# Timer-Ruler_CR2032_on_bottom.net
KiCad netlist of a schematic drawn in EAGLE
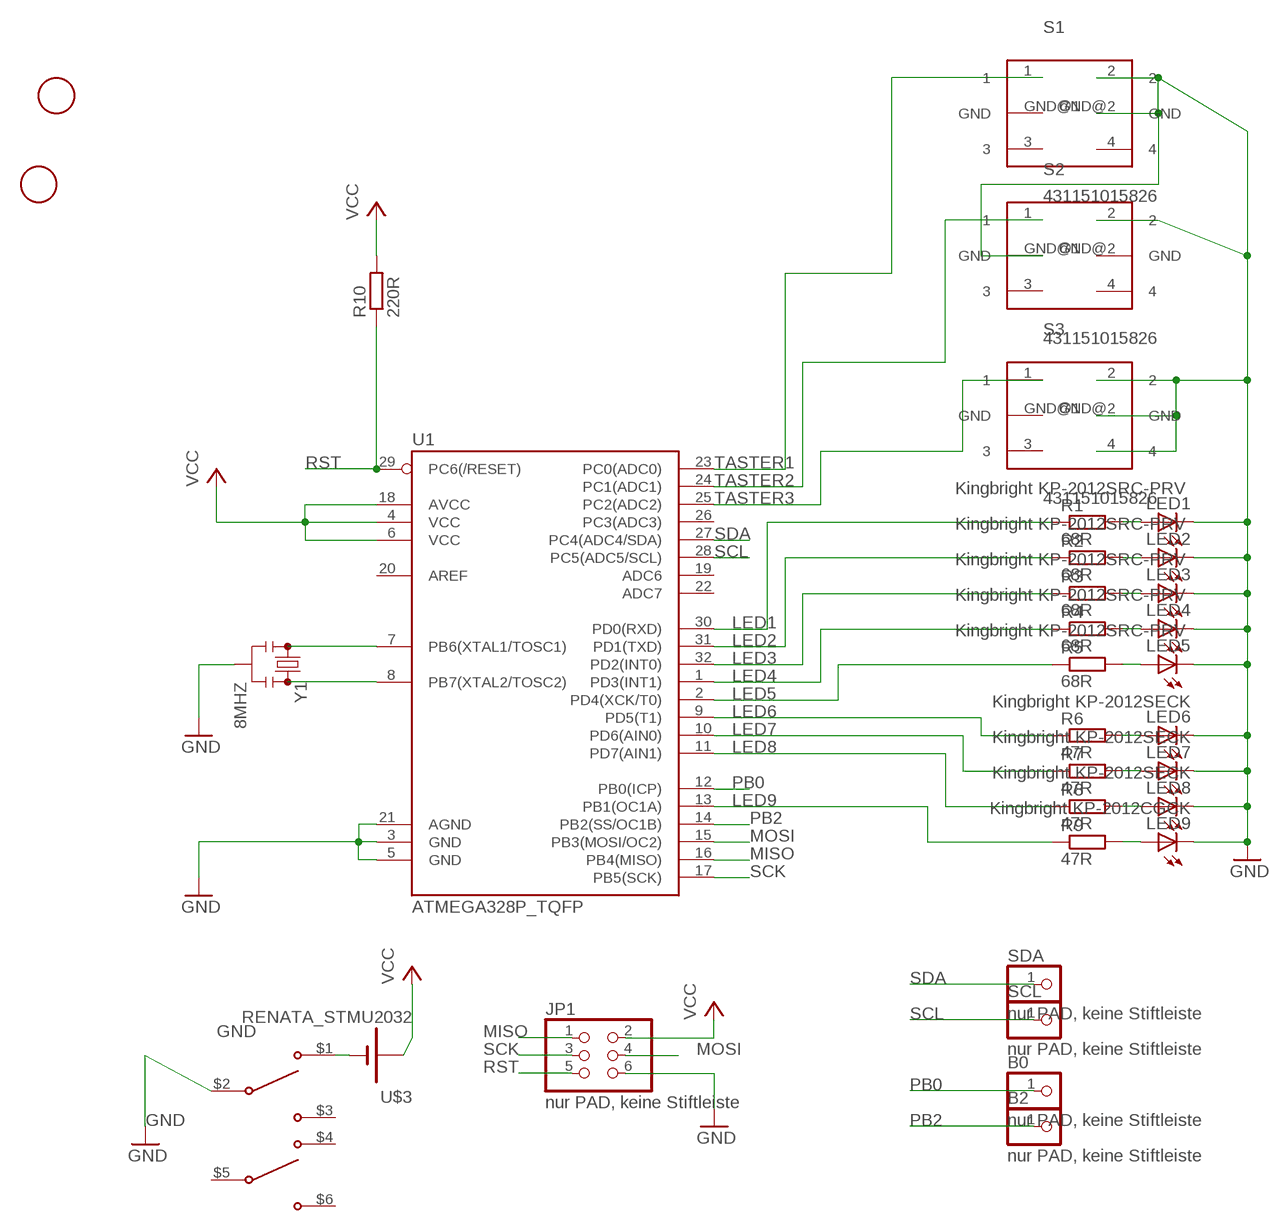
[diagram p0: schematic, sheet 1]

(export (version "E")
  (design (tool "Eeschema 10.0.6"))
  (components
    (comp (ref "B0")
      (value "nur PAD, keine Stiftleiste")
      (footprint "eagle-import:1X01")
      (libsource (lib "eagle-import") (part "PINHD-1X1"))
    )
    (comp (ref "B2")
      (value "nur PAD, keine Stiftleiste")
      (footprint "eagle-import:1X01")
      (libsource (lib "eagle-import") (part "PINHD-1X1"))
    )
    (comp (ref "JP1")
      (value "nur PAD, keine Stiftleiste")
      (footprint "eagle-import:2X03")
      (libsource (lib "eagle-import") (part "PINHD-2X3"))
    )
    (comp (ref "LED1")
      (value "Kingbright KP-2012SRC-PRV")
      (footprint "eagle-import:CHIP-LED0805")
      (libsource (lib "eagle-import") (part "LEDCHIP-LED0805"))
    )
    (comp (ref "LED2")
      (value "Kingbright KP-2012SRC-PRV")
      (footprint "eagle-import:CHIP-LED0805")
      (libsource (lib "eagle-import") (part "LEDCHIP-LED0805"))
    )
    (comp (ref "LED3")
      (value "Kingbright KP-2012SRC-PRV")
      (footprint "eagle-import:CHIP-LED0805")
      (libsource (lib "eagle-import") (part "LEDCHIP-LED0805"))
    )
    (comp (ref "LED4")
      (value "Kingbright KP-2012SRC-PRV")
      (footprint "eagle-import:CHIP-LED0805")
      (libsource (lib "eagle-import") (part "LEDCHIP-LED0805"))
    )
    (comp (ref "LED5")
      (value "Kingbright KP-2012SRC-PRV")
      (footprint "eagle-import:CHIP-LED0805")
      (libsource (lib "eagle-import") (part "LEDCHIP-LED0805"))
    )
    (comp (ref "LED6")
      (value "Kingbright KP-2012SECK")
      (footprint "eagle-import:CHIP-LED0805")
      (libsource (lib "eagle-import") (part "LEDCHIP-LED0805"))
    )
    (comp (ref "LED7")
      (value "Kingbright KP-2012SECK")
      (footprint "eagle-import:CHIP-LED0805")
      (libsource (lib "eagle-import") (part "LEDCHIP-LED0805"))
    )
    (comp (ref "LED8")
      (value "Kingbright KP-2012SECK")
      (footprint "eagle-import:CHIP-LED0805")
      (libsource (lib "eagle-import") (part "LEDCHIP-LED0805"))
    )
    (comp (ref "LED9")
      (value "Kingbright KP-2012CGCK")
      (footprint "eagle-import:CHIP-LED0805")
      (libsource (lib "eagle-import") (part "LEDCHIP-LED0805"))
    )
    (comp (ref "R1")
      (value "68R")
      (footprint "eagle-import:R0402")
      (libsource (lib "eagle-import") (part "R-EU_R0402"))
    )
    (comp (ref "R2")
      (value "68R")
      (footprint "eagle-import:R0402")
      (libsource (lib "eagle-import") (part "R-EU_R0402"))
    )
    (comp (ref "R3")
      (value "68R")
      (footprint "eagle-import:R0402")
      (libsource (lib "eagle-import") (part "R-EU_R0402"))
    )
    (comp (ref "R4")
      (value "68R")
      (footprint "eagle-import:R0402")
      (libsource (lib "eagle-import") (part "R-EU_R0402"))
    )
    (comp (ref "R5")
      (value "68R")
      (footprint "eagle-import:R0402")
      (libsource (lib "eagle-import") (part "R-EU_R0402"))
    )
    (comp (ref "R6")
      (value "47R")
      (footprint "eagle-import:R0402")
      (libsource (lib "eagle-import") (part "R-EU_R0402"))
    )
    (comp (ref "R7")
      (value "47R")
      (footprint "eagle-import:R0402")
      (libsource (lib "eagle-import") (part "R-EU_R0402"))
    )
    (comp (ref "R8")
      (value "47R")
      (footprint "eagle-import:R0402")
      (libsource (lib "eagle-import") (part "R-EU_R0402"))
    )
    (comp (ref "R9")
      (value "47R")
      (footprint "eagle-import:R0402")
      (libsource (lib "eagle-import") (part "R-EU_R0402"))
    )
    (comp (ref "R10")
      (value "220R")
      (footprint "eagle-import:R0402")
      (libsource (lib "eagle-import") (part "R-EU_R0402"))
    )
    (comp (ref "S1")
      (value "431151015826")
      (footprint "eagle-import:431181015816")
      (libsource (lib "eagle-import") (part "431151015826"))
    )
    (comp (ref "S2")
      (value "431151015826")
      (footprint "eagle-import:431181015816")
      (libsource (lib "eagle-import") (part "431151015826"))
    )
    (comp (ref "S3")
      (value "431151015826")
      (footprint "eagle-import:431181015816")
      (libsource (lib "eagle-import") (part "431151015826"))
    )
    (comp (ref "SCL")
      (value "nur PAD, keine Stiftleiste")
      (footprint "eagle-import:1X01")
      (libsource (lib "eagle-import") (part "PINHD-1X1"))
    )
    (comp (ref "SDA")
      (value "nur PAD, keine Stiftleiste")
      (footprint "eagle-import:1X01")
      (libsource (lib "eagle-import") (part "PINHD-1X1"))
    )
    (comp (ref "U$1")
      (value "FIDUCIAL")
      (footprint "eagle-import:FIDUCIAL_1MM")
      (libsource (lib "eagle-import") (part "FIDUCIAL"))
    )
    (comp (ref "U$2")
      (value "FIDUCIAL")
      (footprint "eagle-import:FIDUCIAL_1MM")
      (libsource (lib "eagle-import") (part "FIDUCIAL"))
    )
    (comp (ref "U$3")
      (value "RENATA_STMU2032")
      (footprint "eagle-import:SMTU2032")
      (libsource (lib "eagle-import") (part "RENATA_STMU2032"))
    )
    (comp (ref "U$4")
      (value "C+K_AYZ0202AGRLC")
      (footprint "eagle-import:C+K_AYZ0202AGRLC")
      (libsource (lib "eagle-import") (part "C+K_AYZ0202AGRLC"))
    )
    (comp (ref "U1")
      (value "ATMEGA328P_TQFP")
      (footprint "eagle-import:TQFP32-08")
      (libsource (lib "eagle-import") (part "ATMEGA328P_TQFP"))
    )
    (comp (ref "Y1")
      (value "8MHZ")
      (footprint "eagle-import:RESONATOR-SMD")
      (libsource (lib "eagle-import") (part "RESONATOR8MHZ"))
    )
  )
  (nets
    (net (code "1") (name "/LED1") (class "Default")
      (node (ref "R1") (pin "1") (pinfunction "1_1") (pintype "passive"))
      (node (ref "U1") (pin "30") (pinfunction "PD0(RXD)_30") (pintype "bidirectional"))
    )
    (net (code "2") (name "/LED2") (class "Default")
      (node (ref "R2") (pin "1") (pinfunction "1_1") (pintype "passive"))
      (node (ref "U1") (pin "31") (pinfunction "PD1(TXD)_31") (pintype "bidirectional"))
    )
    (net (code "3") (name "/LED3") (class "Default")
      (node (ref "R3") (pin "1") (pinfunction "1_1") (pintype "passive"))
      (node (ref "U1") (pin "32") (pinfunction "PD2(INT0)_32") (pintype "bidirectional"))
    )
    (net (code "4") (name "/LED4") (class "Default")
      (node (ref "R4") (pin "1") (pinfunction "1_1") (pintype "passive"))
      (node (ref "U1") (pin "1") (pinfunction "PD3(INT1)_1") (pintype "bidirectional"))
    )
    (net (code "5") (name "/LED5") (class "Default")
      (node (ref "R5") (pin "1") (pinfunction "1_1") (pintype "passive"))
      (node (ref "U1") (pin "2") (pinfunction "PD4(XCK/T0)_2") (pintype "bidirectional"))
    )
    (net (code "6") (name "/LED6") (class "Default")
      (node (ref "R6") (pin "1") (pinfunction "1_1") (pintype "passive"))
      (node (ref "U1") (pin "9") (pinfunction "PD5(T1)_9") (pintype "bidirectional"))
    )
    (net (code "7") (name "/LED7") (class "Default")
      (node (ref "R7") (pin "1") (pinfunction "1_1") (pintype "passive"))
      (node (ref "U1") (pin "10") (pinfunction "PD6(AIN0)_10") (pintype "bidirectional"))
    )
    (net (code "8") (name "/LED8") (class "Default")
      (node (ref "R8") (pin "1") (pinfunction "1_1") (pintype "passive"))
      (node (ref "U1") (pin "11") (pinfunction "PD7(AIN1)_11") (pintype "bidirectional"))
    )
    (net (code "9") (name "/LED9") (class "Default")
      (node (ref "R9") (pin "1") (pinfunction "1_1") (pintype "passive"))
      (node (ref "U1") (pin "13") (pinfunction "PB1(OC1A)_13") (pintype "bidirectional"))
    )
    (net (code "10") (name "/MISO") (class "Default")
      (node (ref "JP1") (pin "1") (pinfunction "1_1") (pintype "passive"))
      (node (ref "U1") (pin "16") (pinfunction "PB4(MISO)_16") (pintype "bidirectional"))
    )
    (net (code "11") (name "/MOSI") (class "Default")
      (node (ref "JP1") (pin "4") (pinfunction "4_4") (pintype "passive"))
      (node (ref "U1") (pin "15") (pinfunction "PB3(MOSI/OC2)_15") (pintype "bidirectional"))
    )
    (net (code "12") (name "/PB0") (class "Default")
      (node (ref "B0") (pin "1") (pinfunction "1_1") (pintype "passive"))
      (node (ref "U1") (pin "12") (pinfunction "PB0(ICP)_12") (pintype "bidirectional"))
    )
    (net (code "13") (name "/PB2") (class "Default")
      (node (ref "B2") (pin "1") (pinfunction "1_1") (pintype "passive"))
      (node (ref "U1") (pin "14") (pinfunction "PB2(SS/OC1B)_14") (pintype "bidirectional"))
    )
    (net (code "14") (name "/RST") (class "Default")
      (node (ref "JP1") (pin "5") (pinfunction "5_5") (pintype "passive"))
      (node (ref "R10") (pin "1") (pinfunction "1_1") (pintype "passive"))
      (node (ref "U1") (pin "29") (pinfunction "PC6(/RESET)_29") (pintype "bidirectional"))
    )
    (net (code "15") (name "/SCK") (class "Default")
      (node (ref "JP1") (pin "3") (pinfunction "3_3") (pintype "passive"))
      (node (ref "U1") (pin "17") (pinfunction "PB5(SCK)_17") (pintype "bidirectional"))
    )
    (net (code "16") (name "/SCL") (class "Default")
      (node (ref "SCL") (pin "1") (pinfunction "1_1") (pintype "passive"))
      (node (ref "U1") (pin "28") (pinfunction "PC5(ADC5/SCL)_28") (pintype "bidirectional"))
    )
    (net (code "17") (name "/SDA") (class "Default")
      (node (ref "SDA") (pin "1") (pinfunction "1_1") (pintype "passive"))
      (node (ref "U1") (pin "27") (pinfunction "PC4(ADC4/SDA)_27") (pintype "bidirectional"))
    )
    (net (code "18") (name "/TASTER1") (class "Default")
      (node (ref "S1") (pin "1") (pinfunction "1_1") (pintype "bidirectional"))
      (node (ref "U1") (pin "23") (pinfunction "PC0(ADC0)_23") (pintype "bidirectional"))
    )
    (net (code "19") (name "/TASTER2") (class "Default")
      (node (ref "S2") (pin "1") (pinfunction "1_1") (pintype "bidirectional"))
      (node (ref "U1") (pin "24") (pinfunction "PC1(ADC1)_24") (pintype "bidirectional"))
    )
    (net (code "20") (name "/TASTER3") (class "Default")
      (node (ref "S3") (pin "1") (pinfunction "1_1") (pintype "bidirectional"))
      (node (ref "U1") (pin "25") (pinfunction "PC2(ADC2)_25") (pintype "bidirectional"))
    )
    (net (code "21") (name "GND") (class "Default")
      (node (ref "JP1") (pin "6") (pinfunction "6_6") (pintype "passive"))
      (node (ref "LED1") (pin "C") (pinfunction "C_C") (pintype "passive"))
      (node (ref "LED2") (pin "C") (pinfunction "C_C") (pintype "passive"))
      (node (ref "LED3") (pin "C") (pinfunction "C_C") (pintype "passive"))
      (node (ref "LED4") (pin "C") (pinfunction "C_C") (pintype "passive"))
      (node (ref "LED5") (pin "C") (pinfunction "C_C") (pintype "passive"))
      (node (ref "LED6") (pin "C") (pinfunction "C_C") (pintype "passive"))
      (node (ref "LED7") (pin "C") (pinfunction "C_C") (pintype "passive"))
      (node (ref "LED8") (pin "C") (pinfunction "C_C") (pintype "passive"))
      (node (ref "LED9") (pin "C") (pinfunction "C_C") (pintype "passive"))
      (node (ref "S1") (pin "2") (pinfunction "2_2") (pintype "bidirectional"))
      (node (ref "S1") (pin "GND@2") (pinfunction "GND_GND@2") (pintype "bidirectional"))
      (node (ref "S2") (pin "2") (pinfunction "2_2") (pintype "bidirectional"))
      (node (ref "S2") (pin "GND@1") (pinfunction "GND_GND@1") (pintype "bidirectional"))
      (node (ref "S3") (pin "2") (pinfunction "2_2") (pintype "bidirectional"))
      (node (ref "S3") (pin "4") (pinfunction "4_4") (pintype "bidirectional"))
      (node (ref "S3") (pin "GND@2") (pinfunction "GND_GND@2") (pintype "bidirectional"))
      (node (ref "U$4") (pin "$2") (pinfunction "2_$2") (pintype "bidirectional"))
      (node (ref "U1") (pin "21") (pinfunction "AGND_21") (pintype "bidirectional"))
      (node (ref "U1") (pin "3") (pinfunction "GND_3") (pintype "bidirectional"))
      (node (ref "U1") (pin "5") (pinfunction "GND_5") (pintype "bidirectional"))
      (node (ref "Y1") (pin "2") (pinfunction "2_2") (pintype "passive"))
    )
    (net (code "22") (name "Net-(LED1-PadA)") (class "Default")
      (node (ref "LED1") (pin "A") (pinfunction "A_A") (pintype "passive"))
      (node (ref "R1") (pin "2") (pinfunction "2_2") (pintype "passive"))
    )
    (net (code "23") (name "Net-(LED2-PadA)") (class "Default")
      (node (ref "LED2") (pin "A") (pinfunction "A_A") (pintype "passive"))
      (node (ref "R2") (pin "2") (pinfunction "2_2") (pintype "passive"))
    )
    (net (code "24") (name "Net-(LED3-PadA)") (class "Default")
      (node (ref "LED3") (pin "A") (pinfunction "A_A") (pintype "passive"))
      (node (ref "R3") (pin "2") (pinfunction "2_2") (pintype "passive"))
    )
    (net (code "25") (name "Net-(LED4-PadA)") (class "Default")
      (node (ref "LED4") (pin "A") (pinfunction "A_A") (pintype "passive"))
      (node (ref "R4") (pin "2") (pinfunction "2_2") (pintype "passive"))
    )
    (net (code "26") (name "Net-(LED5-PadA)") (class "Default")
      (node (ref "LED5") (pin "A") (pinfunction "A_A") (pintype "passive"))
      (node (ref "R5") (pin "2") (pinfunction "2_2") (pintype "passive"))
    )
    (net (code "27") (name "Net-(LED6-PadA)") (class "Default")
      (node (ref "LED6") (pin "A") (pinfunction "A_A") (pintype "passive"))
      (node (ref "R6") (pin "2") (pinfunction "2_2") (pintype "passive"))
    )
    (net (code "28") (name "Net-(LED7-PadA)") (class "Default")
      (node (ref "LED7") (pin "A") (pinfunction "A_A") (pintype "passive"))
      (node (ref "R7") (pin "2") (pinfunction "2_2") (pintype "passive"))
    )
    (net (code "29") (name "Net-(LED8-PadA)") (class "Default")
      (node (ref "LED8") (pin "A") (pinfunction "A_A") (pintype "passive"))
      (node (ref "R8") (pin "2") (pinfunction "2_2") (pintype "passive"))
    )
    (net (code "30") (name "Net-(LED9-PadA)") (class "Default")
      (node (ref "LED9") (pin "A") (pinfunction "A_A") (pintype "passive"))
      (node (ref "R9") (pin "2") (pinfunction "2_2") (pintype "passive"))
    )
    (net (code "31") (name "Net-(U$4-1)") (class "Default")
      (node (ref "U$3") (pin "-") (pinfunction "-_-") (pintype "power_in"))
      (node (ref "U$4") (pin "$1") (pinfunction "1_$1") (pintype "bidirectional"))
    )
    (net (code "32") (name "Net-(U1-PB6(XTAL1{slash}TOSC1))") (class "Default")
      (node (ref "U1") (pin "7") (pinfunction "PB6(XTAL1/TOSC1)_7") (pintype "bidirectional"))
      (node (ref "Y1") (pin "1") (pinfunction "1_1") (pintype "passive"))
    )
    (net (code "33") (name "Net-(U1-PB7(XTAL2{slash}TOSC2))") (class "Default")
      (node (ref "U1") (pin "8") (pinfunction "PB7(XTAL2/TOSC2)_8") (pintype "bidirectional"))
      (node (ref "Y1") (pin "3") (pinfunction "3_3") (pintype "passive"))
    )
    (net (code "34") (name "VCC") (class "Default")
      (node (ref "JP1") (pin "2") (pinfunction "2_2") (pintype "passive"))
      (node (ref "R10") (pin "2") (pinfunction "2_2") (pintype "passive"))
      (node (ref "U$3") (pin "+") (pinfunction "+_+") (pintype "power_in"))
      (node (ref "U1") (pin "18") (pinfunction "AVCC_18") (pintype "bidirectional"))
      (node (ref "U1") (pin "4") (pinfunction "VCC_4") (pintype "bidirectional"))
      (node (ref "U1") (pin "6") (pinfunction "VCC_6") (pintype "bidirectional"))
    )
    (net (code "35") (name "unconnected-(S1-GND-PadGND@1)") (class "Default")
      (node (ref "S1") (pin "GND@1") (pinfunction "GND_GND@1") (pintype "bidirectional"))
    )
    (net (code "36") (name "unconnected-(S1-Pad3)") (class "Default")
      (node (ref "S1") (pin "3") (pinfunction "3_3") (pintype "bidirectional"))
    )
    (net (code "37") (name "unconnected-(S1-Pad4)") (class "Default")
      (node (ref "S1") (pin "4") (pinfunction "4_4") (pintype "bidirectional"))
    )
    (net (code "38") (name "unconnected-(S2-GND-PadGND@2)") (class "Default")
      (node (ref "S2") (pin "GND@2") (pinfunction "GND_GND@2") (pintype "bidirectional"))
    )
    (net (code "39") (name "unconnected-(S2-Pad3)") (class "Default")
      (node (ref "S2") (pin "3") (pinfunction "3_3") (pintype "bidirectional"))
    )
    (net (code "40") (name "unconnected-(S2-Pad4)") (class "Default")
      (node (ref "S2") (pin "4") (pinfunction "4_4") (pintype "bidirectional"))
    )
    (net (code "41") (name "unconnected-(S3-GND-PadGND@1)") (class "Default")
      (node (ref "S3") (pin "GND@1") (pinfunction "GND_GND@1") (pintype "bidirectional"))
    )
    (net (code "42") (name "unconnected-(S3-Pad3)") (class "Default")
      (node (ref "S3") (pin "3") (pinfunction "3_3") (pintype "bidirectional"))
    )
    (net (code "43") (name "unconnected-(U$4-3-Pad$3)") (class "Default")
      (node (ref "U$4") (pin "$3") (pinfunction "3_$3") (pintype "bidirectional"))
    )
    (net (code "44") (name "unconnected-(U$4-4-Pad$4)") (class "Default")
      (node (ref "U$4") (pin "$4") (pinfunction "4_$4") (pintype "bidirectional"))
    )
    (net (code "45") (name "unconnected-(U$4-5-Pad$5)") (class "Default")
      (node (ref "U$4") (pin "$5") (pinfunction "5_$5") (pintype "bidirectional"))
    )
    (net (code "46") (name "unconnected-(U$4-6-Pad$6)") (class "Default")
      (node (ref "U$4") (pin "$6") (pinfunction "6_$6") (pintype "bidirectional"))
    )
    (net (code "47") (name "unconnected-(U1-ADC6-Pad19)") (class "Default")
      (node (ref "U1") (pin "19") (pinfunction "ADC6_19") (pintype "bidirectional"))
    )
    (net (code "48") (name "unconnected-(U1-ADC7-Pad22)") (class "Default")
      (node (ref "U1") (pin "22") (pinfunction "ADC7_22") (pintype "bidirectional"))
    )
    (net (code "49") (name "unconnected-(U1-AREF-Pad20)") (class "Default")
      (node (ref "U1") (pin "20") (pinfunction "AREF_20") (pintype "bidirectional"))
    )
    (net (code "50") (name "unconnected-(U1-PC3(ADC3)-Pad26)") (class "Default")
      (node (ref "U1") (pin "26") (pinfunction "PC3(ADC3)_26") (pintype "bidirectional"))
    )
  )
)
